# Solenoids.net
KiCad netlist of a schematic drawn in Altium Designer
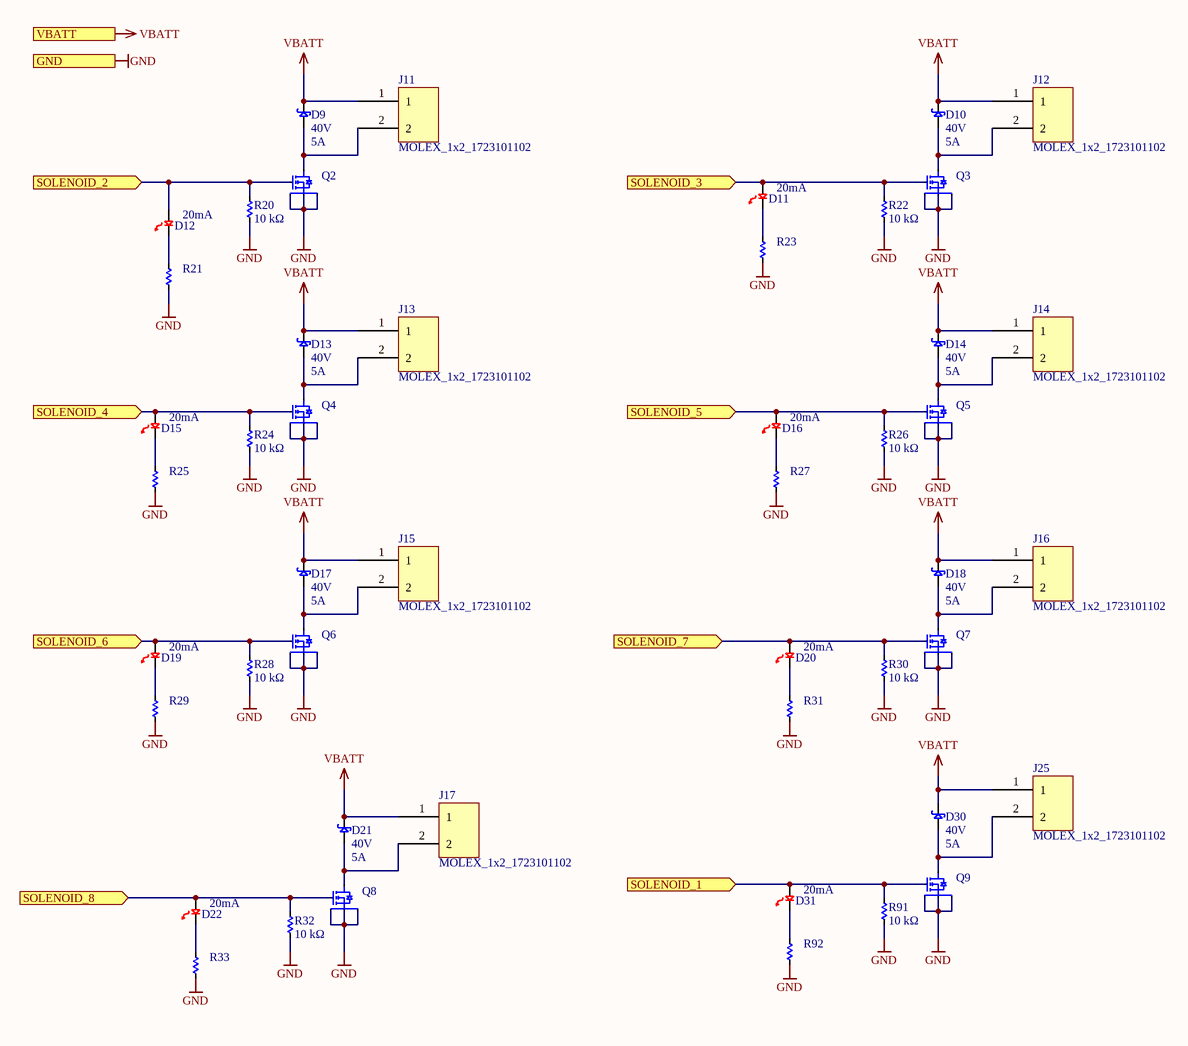
[diagram p0: Solenoids.SchDoc]

(export (version "E")
  (design (tool "Eeschema 10.0.6"))
  (components
    (comp (ref "D9")
      (value "SCHOTTKY_B540C-13-F")
      (footprint "SMC")
      (description "DIODE SCHOTTKY 40V 5A SMC")
      (fields
        (field (name "MANUFACTURER") "Diodes Inc")
        (field (name "MANUFACTURER PART NUMBER") "B540C-13-F")
        (field (name "VOLTAGE - DC REVERSE (VR) (MAX)") "40V")
        (field (name "CURRENT - AVERAGE RECTIFIED (IO)") "5A")
      )
      (libsource (lib "Stanford Student Space Initiative") (part "Symbol"))
    )
    (comp (ref "D10")
      (value "SCHOTTKY_B540C-13-F")
      (footprint "SMC")
      (description "DIODE SCHOTTKY 40V 5A SMC")
      (fields
        (field (name "MANUFACTURER") "Diodes Inc")
        (field (name "MANUFACTURER PART NUMBER") "B540C-13-F")
        (field (name "VOLTAGE - DC REVERSE (VR) (MAX)") "40V")
        (field (name "CURRENT - AVERAGE RECTIFIED (IO)") "5A")
      )
      (libsource (lib "Stanford Student Space Initiative") (part "Symbol"))
    )
    (comp (ref "D11")
      (value "LED_LY974")
      (footprint "0805_Diode")
      (description "LED 0805 RED 20MA")
      (fields
        (field (name "MANUFACTURER") "OSRAM Opto Semiconductors Inc")
        (field (name "MANUFACTURER PART NUMBER") "LH R974-LP-1")
        (field (name "CURRENT - TEST") "20mA")
      )
      (libsource (lib "Stanford Student Space Initiative") (part "LED_LY974"))
    )
    (comp (ref "D12")
      (value "LED_LY974")
      (footprint "0805_Diode")
      (description "LED 0805 RED 20MA")
      (fields
        (field (name "MANUFACTURER") "OSRAM Opto Semiconductors Inc")
        (field (name "MANUFACTURER PART NUMBER") "LH R974-LP-1")
        (field (name "CURRENT - TEST") "20mA")
      )
      (libsource (lib "Stanford Student Space Initiative") (part "LED_LY974"))
    )
    (comp (ref "D13")
      (value "SCHOTTKY_B540C-13-F")
      (footprint "SMC")
      (description "DIODE SCHOTTKY 40V 5A SMC")
      (fields
        (field (name "MANUFACTURER") "Diodes Inc")
        (field (name "MANUFACTURER PART NUMBER") "B540C-13-F")
        (field (name "VOLTAGE - DC REVERSE (VR) (MAX)") "40V")
        (field (name "CURRENT - AVERAGE RECTIFIED (IO)") "5A")
      )
      (libsource (lib "Stanford Student Space Initiative") (part "Symbol"))
    )
    (comp (ref "D14")
      (value "SCHOTTKY_B540C-13-F")
      (footprint "SMC")
      (description "DIODE SCHOTTKY 40V 5A SMC")
      (fields
        (field (name "MANUFACTURER") "Diodes Inc")
        (field (name "MANUFACTURER PART NUMBER") "B540C-13-F")
        (field (name "VOLTAGE - DC REVERSE (VR) (MAX)") "40V")
        (field (name "CURRENT - AVERAGE RECTIFIED (IO)") "5A")
      )
      (libsource (lib "Stanford Student Space Initiative") (part "Symbol"))
    )
    (comp (ref "D15")
      (value "LED_LY974")
      (footprint "0805_Diode")
      (description "LED 0805 RED 20MA")
      (fields
        (field (name "MANUFACTURER") "OSRAM Opto Semiconductors Inc")
        (field (name "MANUFACTURER PART NUMBER") "LH R974-LP-1")
        (field (name "CURRENT - TEST") "20mA")
      )
      (libsource (lib "Stanford Student Space Initiative") (part "LED_LY974"))
    )
    (comp (ref "D16")
      (value "LED_LY974")
      (footprint "0805_Diode")
      (description "LED 0805 RED 20MA")
      (fields
        (field (name "MANUFACTURER") "OSRAM Opto Semiconductors Inc")
        (field (name "MANUFACTURER PART NUMBER") "LH R974-LP-1")
        (field (name "CURRENT - TEST") "20mA")
      )
      (libsource (lib "Stanford Student Space Initiative") (part "LED_LY974"))
    )
    (comp (ref "D17")
      (value "SCHOTTKY_B540C-13-F")
      (footprint "SMC")
      (description "DIODE SCHOTTKY 40V 5A SMC")
      (fields
        (field (name "MANUFACTURER") "Diodes Inc")
        (field (name "MANUFACTURER PART NUMBER") "B540C-13-F")
        (field (name "VOLTAGE - DC REVERSE (VR) (MAX)") "40V")
        (field (name "CURRENT - AVERAGE RECTIFIED (IO)") "5A")
      )
      (libsource (lib "Stanford Student Space Initiative") (part "Symbol"))
    )
    (comp (ref "D18")
      (value "SCHOTTKY_B540C-13-F")
      (footprint "SMC")
      (description "DIODE SCHOTTKY 40V 5A SMC")
      (fields
        (field (name "MANUFACTURER") "Diodes Inc")
        (field (name "MANUFACTURER PART NUMBER") "B540C-13-F")
        (field (name "VOLTAGE - DC REVERSE (VR) (MAX)") "40V")
        (field (name "CURRENT - AVERAGE RECTIFIED (IO)") "5A")
      )
      (libsource (lib "Stanford Student Space Initiative") (part "Symbol"))
    )
    (comp (ref "D19")
      (value "LED_LY974")
      (footprint "0805_Diode")
      (description "LED 0805 RED 20MA")
      (fields
        (field (name "MANUFACTURER") "OSRAM Opto Semiconductors Inc")
        (field (name "MANUFACTURER PART NUMBER") "LH R974-LP-1")
        (field (name "CURRENT - TEST") "20mA")
      )
      (libsource (lib "Stanford Student Space Initiative") (part "LED_LY974"))
    )
    (comp (ref "D20")
      (value "LED_LY974")
      (footprint "0805_Diode")
      (description "LED 0805 RED 20MA")
      (fields
        (field (name "MANUFACTURER") "OSRAM Opto Semiconductors Inc")
        (field (name "MANUFACTURER PART NUMBER") "LH R974-LP-1")
        (field (name "CURRENT - TEST") "20mA")
      )
      (libsource (lib "Stanford Student Space Initiative") (part "LED_LY974"))
    )
    (comp (ref "D21")
      (value "SCHOTTKY_B540C-13-F")
      (footprint "SMC")
      (description "DIODE SCHOTTKY 40V 5A SMC")
      (fields
        (field (name "MANUFACTURER") "Diodes Inc")
        (field (name "MANUFACTURER PART NUMBER") "B540C-13-F")
        (field (name "VOLTAGE - DC REVERSE (VR) (MAX)") "40V")
        (field (name "CURRENT - AVERAGE RECTIFIED (IO)") "5A")
      )
      (libsource (lib "Stanford Student Space Initiative") (part "Symbol"))
    )
    (comp (ref "D22")
      (value "LED_LY974")
      (footprint "0805_Diode")
      (description "LED 0805 RED 20MA")
      (fields
        (field (name "MANUFACTURER") "OSRAM Opto Semiconductors Inc")
        (field (name "MANUFACTURER PART NUMBER") "LH R974-LP-1")
        (field (name "CURRENT - TEST") "20mA")
      )
      (libsource (lib "Stanford Student Space Initiative") (part "LED_LY974"))
    )
    (comp (ref "D30")
      (value "SCHOTTKY_B540C-13-F")
      (footprint "SMC")
      (description "DIODE SCHOTTKY 40V 5A SMC")
      (fields
        (field (name "MANUFACTURER") "Diodes Inc")
        (field (name "MANUFACTURER PART NUMBER") "B540C-13-F")
        (field (name "VOLTAGE - DC REVERSE (VR) (MAX)") "40V")
        (field (name "CURRENT - AVERAGE RECTIFIED (IO)") "5A")
      )
      (libsource (lib "Stanford Student Space Initiative") (part "Symbol"))
    )
    (comp (ref "D31")
      (value "LED_LY974")
      (footprint "0805_Diode")
      (description "LED 0805 RED 20MA")
      (fields
        (field (name "MANUFACTURER") "OSRAM Opto Semiconductors Inc")
        (field (name "MANUFACTURER PART NUMBER") "LH R974-LP-1")
        (field (name "CURRENT - TEST") "20mA")
      )
      (libsource (lib "Stanford Student Space Initiative") (part "LED_LY974"))
    )
    (comp (ref "J11")
      (value "MOLEX_1x2_1723101102")
      (footprint "MOLEX_1x2_1723101102")
      (description "ULTRAFIT CONN HEADER R/A 2POS 3.5MM")
      (libsource (lib "Stanford Student Space Initiative") (part "MOLEX_1x2_1723101102"))
    )
    (comp (ref "J12")
      (value "MOLEX_1x2_1723101102")
      (footprint "MOLEX_1x2_1723101102")
      (description "ULTRAFIT CONN HEADER R/A 2POS 3.5MM")
      (libsource (lib "Stanford Student Space Initiative") (part "MOLEX_1x2_1723101102"))
    )
    (comp (ref "J13")
      (value "MOLEX_1x2_1723101102")
      (footprint "MOLEX_1x2_1723101102")
      (description "ULTRAFIT CONN HEADER R/A 2POS 3.5MM")
      (libsource (lib "Stanford Student Space Initiative") (part "MOLEX_1x2_1723101102"))
    )
    (comp (ref "J14")
      (value "MOLEX_1x2_1723101102")
      (footprint "MOLEX_1x2_1723101102")
      (description "ULTRAFIT CONN HEADER R/A 2POS 3.5MM")
      (libsource (lib "Stanford Student Space Initiative") (part "MOLEX_1x2_1723101102"))
    )
    (comp (ref "J15")
      (value "MOLEX_1x2_1723101102")
      (footprint "MOLEX_1x2_1723101102")
      (description "ULTRAFIT CONN HEADER R/A 2POS 3.5MM")
      (libsource (lib "Stanford Student Space Initiative") (part "MOLEX_1x2_1723101102"))
    )
    (comp (ref "J16")
      (value "MOLEX_1x2_1723101102")
      (footprint "MOLEX_1x2_1723101102")
      (description "ULTRAFIT CONN HEADER R/A 2POS 3.5MM")
      (libsource (lib "Stanford Student Space Initiative") (part "MOLEX_1x2_1723101102"))
    )
    (comp (ref "J17")
      (value "MOLEX_1x2_1723101102")
      (footprint "MOLEX_1x2_1723101102")
      (description "ULTRAFIT CONN HEADER R/A 2POS 3.5MM")
      (libsource (lib "Stanford Student Space Initiative") (part "MOLEX_1x2_1723101102"))
    )
    (comp (ref "J25")
      (value "MOLEX_1x2_1723101102")
      (footprint "MOLEX_1x2_1723101102")
      (description "ULTRAFIT CONN HEADER R/A 2POS 3.5MM")
      (libsource (lib "Stanford Student Space Initiative") (part "MOLEX_1x2_1723101102"))
    )
    (comp (ref "Q2")
      (value "NFET_CSD16323Q3")
      (footprint "8-VSON")
      (description "MOSFET N-CH 25V 3.3X3.3 8-SON")
      (fields
        (field (name "MANUFACTURER") "Texas Instruments")
        (field (name "MANUFACTURER PART NUMBER") "CSD16323Q3")
      )
      (libsource (lib "Stanford Student Space Initiative") (part "NFET_CSD16323Q3"))
    )
    (comp (ref "Q3")
      (value "NFET_CSD16323Q3")
      (footprint "8-VSON")
      (description "MOSFET N-CH 25V 3.3X3.3 8-SON")
      (fields
        (field (name "MANUFACTURER") "Texas Instruments")
        (field (name "MANUFACTURER PART NUMBER") "CSD16323Q3")
      )
      (libsource (lib "Stanford Student Space Initiative") (part "NFET_CSD16323Q3"))
    )
    (comp (ref "Q4")
      (value "NFET_CSD16323Q3")
      (footprint "8-VSON")
      (description "MOSFET N-CH 25V 3.3X3.3 8-SON")
      (fields
        (field (name "MANUFACTURER") "Texas Instruments")
        (field (name "MANUFACTURER PART NUMBER") "CSD16323Q3")
      )
      (libsource (lib "Stanford Student Space Initiative") (part "NFET_CSD16323Q3"))
    )
    (comp (ref "Q5")
      (value "NFET_CSD16323Q3")
      (footprint "8-VSON")
      (description "MOSFET N-CH 25V 3.3X3.3 8-SON")
      (fields
        (field (name "MANUFACTURER") "Texas Instruments")
        (field (name "MANUFACTURER PART NUMBER") "CSD16323Q3")
      )
      (libsource (lib "Stanford Student Space Initiative") (part "NFET_CSD16323Q3"))
    )
    (comp (ref "Q6")
      (value "NFET_CSD16323Q3")
      (footprint "8-VSON")
      (description "MOSFET N-CH 25V 3.3X3.3 8-SON")
      (fields
        (field (name "MANUFACTURER") "Texas Instruments")
        (field (name "MANUFACTURER PART NUMBER") "CSD16323Q3")
      )
      (libsource (lib "Stanford Student Space Initiative") (part "NFET_CSD16323Q3"))
    )
    (comp (ref "Q7")
      (value "NFET_CSD16323Q3")
      (footprint "8-VSON")
      (description "MOSFET N-CH 25V 3.3X3.3 8-SON")
      (fields
        (field (name "MANUFACTURER") "Texas Instruments")
        (field (name "MANUFACTURER PART NUMBER") "CSD16323Q3")
      )
      (libsource (lib "Stanford Student Space Initiative") (part "NFET_CSD16323Q3"))
    )
    (comp (ref "Q8")
      (value "NFET_CSD16323Q3")
      (footprint "8-VSON")
      (description "MOSFET N-CH 25V 3.3X3.3 8-SON")
      (fields
        (field (name "MANUFACTURER") "Texas Instruments")
        (field (name "MANUFACTURER PART NUMBER") "CSD16323Q3")
      )
      (libsource (lib "Stanford Student Space Initiative") (part "NFET_CSD16323Q3"))
    )
    (comp (ref "Q9")
      (value "NFET_CSD16323Q3")
      (footprint "8-VSON")
      (description "MOSFET N-CH 25V 3.3X3.3 8-SON")
      (fields
        (field (name "MANUFACTURER PART NUMBER") "CSD16323Q3")
        (field (name "MANUFACTURER") "Texas Instruments")
      )
      (libsource (lib "Stanford Student Space Initiative") (part "NFET_CSD16323Q3"))
    )
    (comp (ref "R20")
      (value "311-10.0KHRCT-ND")
      (footprint "R0603")
      (description "RES SMD 10K OHM 1% 1/10W 0603")
      (fields
        (field (name "RESISTANCE") "10 kΩ")
        (field (name "MANUFACTURER PART NUMBER") "RC0603FR-0710KL")
        (field (name "MANUFACTURER") "Yageo")
      )
      (libsource (lib "Stanford Student Space Initiative") (part "__template_resistor"))
    )
    (comp (ref "R21")
      (value "311-1.00KHRCT-ND")
      (footprint "R0603")
      (description "RES SMD 1K OHM 1% 1/10W 0603")
      (fields (field (name "MANUFACTURER") "Yageo") (field (name "TOLERANCE") "±1%"))
      (libsource (lib "Stanford Student Space Initiative") (part "__template_resistor"))
    )
    (comp (ref "R22")
      (value "311-10.0KHRCT-ND")
      (footprint "R0603")
      (description "RES SMD 10K OHM 1% 1/10W 0603")
      (fields
        (field (name "RESISTANCE") "10 kΩ")
        (field (name "MANUFACTURER PART NUMBER") "RC0603FR-0710KL")
        (field (name "MANUFACTURER") "Yageo")
      )
      (libsource (lib "Stanford Student Space Initiative") (part "__template_resistor"))
    )
    (comp (ref "R23")
      (value "311-1.00KHRCT-ND")
      (footprint "R0603")
      (description "RES SMD 1K OHM 1% 1/10W 0603")
      (fields (field (name "MANUFACTURER") "Yageo") (field (name "TOLERANCE") "±1%"))
      (libsource (lib "Stanford Student Space Initiative") (part "__template_resistor"))
    )
    (comp (ref "R24")
      (value "311-10.0KHRCT-ND")
      (footprint "R0603")
      (description "RES SMD 10K OHM 1% 1/10W 0603")
      (fields
        (field (name "RESISTANCE") "10 kΩ")
        (field (name "MANUFACTURER PART NUMBER") "RC0603FR-0710KL")
        (field (name "MANUFACTURER") "Yageo")
      )
      (libsource (lib "Stanford Student Space Initiative") (part "__template_resistor"))
    )
    (comp (ref "R25")
      (value "311-1.00KHRCT-ND")
      (footprint "R0603")
      (description "RES SMD 1K OHM 1% 1/10W 0603")
      (fields (field (name "MANUFACTURER") "Yageo") (field (name "TOLERANCE") "±1%"))
      (libsource (lib "Stanford Student Space Initiative") (part "__template_resistor"))
    )
    (comp (ref "R26")
      (value "311-10.0KHRCT-ND")
      (footprint "R0603")
      (description "RES SMD 10K OHM 1% 1/10W 0603")
      (fields
        (field (name "RESISTANCE") "10 kΩ")
        (field (name "MANUFACTURER PART NUMBER") "RC0603FR-0710KL")
        (field (name "MANUFACTURER") "Yageo")
      )
      (libsource (lib "Stanford Student Space Initiative") (part "__template_resistor"))
    )
    (comp (ref "R27")
      (value "311-1.00KHRCT-ND")
      (footprint "R0603")
      (description "RES SMD 1K OHM 1% 1/10W 0603")
      (fields (field (name "MANUFACTURER") "Yageo") (field (name "TOLERANCE") "±1%"))
      (libsource (lib "Stanford Student Space Initiative") (part "__template_resistor"))
    )
    (comp (ref "R28")
      (value "311-10.0KHRCT-ND")
      (footprint "R0603")
      (description "RES SMD 10K OHM 1% 1/10W 0603")
      (fields
        (field (name "RESISTANCE") "10 kΩ")
        (field (name "MANUFACTURER PART NUMBER") "RC0603FR-0710KL")
        (field (name "MANUFACTURER") "Yageo")
      )
      (libsource (lib "Stanford Student Space Initiative") (part "__template_resistor"))
    )
    (comp (ref "R29")
      (value "311-1.00KHRCT-ND")
      (footprint "R0603")
      (description "RES SMD 1K OHM 1% 1/10W 0603")
      (fields (field (name "MANUFACTURER") "Yageo") (field (name "TOLERANCE") "±1%"))
      (libsource (lib "Stanford Student Space Initiative") (part "__template_resistor"))
    )
    (comp (ref "R30")
      (value "311-10.0KHRCT-ND")
      (footprint "R0603")
      (description "RES SMD 10K OHM 1% 1/10W 0603")
      (fields
        (field (name "RESISTANCE") "10 kΩ")
        (field (name "MANUFACTURER PART NUMBER") "RC0603FR-0710KL")
        (field (name "MANUFACTURER") "Yageo")
      )
      (libsource (lib "Stanford Student Space Initiative") (part "__template_resistor"))
    )
    (comp (ref "R31")
      (value "311-1.00KHRCT-ND")
      (footprint "R0603")
      (description "RES SMD 1K OHM 1% 1/10W 0603")
      (fields (field (name "MANUFACTURER") "Yageo") (field (name "TOLERANCE") "±1%"))
      (libsource (lib "Stanford Student Space Initiative") (part "__template_resistor"))
    )
    (comp (ref "R32")
      (value "311-10.0KHRCT-ND")
      (footprint "R0603")
      (description "RES SMD 10K OHM 1% 1/10W 0603")
      (fields
        (field (name "RESISTANCE") "10 kΩ")
        (field (name "MANUFACTURER PART NUMBER") "RC0603FR-0710KL")
        (field (name "MANUFACTURER") "Yageo")
      )
      (libsource (lib "Stanford Student Space Initiative") (part "__template_resistor"))
    )
    (comp (ref "R33")
      (value "311-1.00KHRCT-ND")
      (footprint "R0603")
      (description "RES SMD 1K OHM 1% 1/10W 0603")
      (fields (field (name "MANUFACTURER") "Yageo") (field (name "TOLERANCE") "±1%"))
      (libsource (lib "Stanford Student Space Initiative") (part "__template_resistor"))
    )
    (comp (ref "R91")
      (value "311-10.0KHRCT-ND")
      (footprint "R0603")
      (description "RES SMD 10K OHM 1% 1/10W 0603")
      (fields
        (field (name "RESISTANCE") "10 kΩ")
        (field (name "MANUFACTURER PART NUMBER") "RC0603FR-0710KL")
        (field (name "MANUFACTURER") "Yageo")
      )
      (libsource (lib "Stanford Student Space Initiative") (part "__template_resistor"))
    )
    (comp (ref "R92")
      (value "311-1.00KHRCT-ND")
      (footprint "R0603")
      (description "RES SMD 1K OHM 1% 1/10W 0603")
      (fields (field (name "MANUFACTURER") "Yageo") (field (name "TOLERANCE") "±1%"))
      (libsource (lib "Stanford Student Space Initiative") (part "__template_resistor"))
    )
  )
  (nets
    (net (code "1") (name "/SOLENOID_1") (class "Default")
      (node (ref "D31") (pin "2") (pintype "passive"))
      (node (ref "Q9") (pin "4") (pinfunction "G_4") (pintype "passive"))
      (node (ref "R91") (pin "2") (pintype "passive"))
    )
    (net (code "2") (name "/SOLENOID_2") (class "Default")
      (node (ref "D12") (pin "2") (pintype "passive"))
      (node (ref "Q2") (pin "4") (pinfunction "G_4") (pintype "passive"))
      (node (ref "R20") (pin "2") (pintype "passive"))
    )
    (net (code "3") (name "/SOLENOID_3") (class "Default")
      (node (ref "D11") (pin "2") (pintype "passive"))
      (node (ref "Q3") (pin "4") (pinfunction "G_4") (pintype "passive"))
      (node (ref "R22") (pin "2") (pintype "passive"))
    )
    (net (code "4") (name "/SOLENOID_4") (class "Default")
      (node (ref "D15") (pin "2") (pintype "passive"))
      (node (ref "Q4") (pin "4") (pinfunction "G_4") (pintype "passive"))
      (node (ref "R24") (pin "2") (pintype "passive"))
    )
    (net (code "5") (name "/SOLENOID_5") (class "Default")
      (node (ref "D16") (pin "2") (pintype "passive"))
      (node (ref "Q5") (pin "4") (pinfunction "G_4") (pintype "passive"))
      (node (ref "R26") (pin "2") (pintype "passive"))
    )
    (net (code "6") (name "/SOLENOID_6") (class "Default")
      (node (ref "D19") (pin "2") (pintype "passive"))
      (node (ref "Q6") (pin "4") (pinfunction "G_4") (pintype "passive"))
      (node (ref "R28") (pin "2") (pintype "passive"))
    )
    (net (code "7") (name "/SOLENOID_7") (class "Default")
      (node (ref "D20") (pin "2") (pintype "passive"))
      (node (ref "Q7") (pin "4") (pinfunction "G_4") (pintype "passive"))
      (node (ref "R30") (pin "2") (pintype "passive"))
    )
    (net (code "8") (name "/SOLENOID_8") (class "Default")
      (node (ref "D22") (pin "2") (pintype "passive"))
      (node (ref "Q8") (pin "4") (pinfunction "G_4") (pintype "passive"))
      (node (ref "R32") (pin "2") (pintype "passive"))
    )
    (net (code "9") (name "GND") (class "Default")
      (node (ref "Q2") (pin "1") (pinfunction "S_1") (pintype "passive"))
      (node (ref "Q2") (pin "2") (pinfunction "S_2") (pintype "passive"))
      (node (ref "Q2") (pin "3") (pinfunction "S_3") (pintype "passive"))
      (node (ref "Q3") (pin "1") (pinfunction "S_1") (pintype "passive"))
      (node (ref "Q3") (pin "2") (pinfunction "S_2") (pintype "passive"))
      (node (ref "Q3") (pin "3") (pinfunction "S_3") (pintype "passive"))
      (node (ref "Q4") (pin "1") (pinfunction "S_1") (pintype "passive"))
      (node (ref "Q4") (pin "2") (pinfunction "S_2") (pintype "passive"))
      (node (ref "Q4") (pin "3") (pinfunction "S_3") (pintype "passive"))
      (node (ref "Q5") (pin "1") (pinfunction "S_1") (pintype "passive"))
      (node (ref "Q5") (pin "2") (pinfunction "S_2") (pintype "passive"))
      (node (ref "Q5") (pin "3") (pinfunction "S_3") (pintype "passive"))
      (node (ref "Q6") (pin "1") (pinfunction "S_1") (pintype "passive"))
      (node (ref "Q6") (pin "2") (pinfunction "S_2") (pintype "passive"))
      (node (ref "Q6") (pin "3") (pinfunction "S_3") (pintype "passive"))
      (node (ref "Q7") (pin "1") (pinfunction "S_1") (pintype "passive"))
      (node (ref "Q7") (pin "2") (pinfunction "S_2") (pintype "passive"))
      (node (ref "Q7") (pin "3") (pinfunction "S_3") (pintype "passive"))
      (node (ref "Q8") (pin "1") (pinfunction "S_1") (pintype "passive"))
      (node (ref "Q8") (pin "2") (pinfunction "S_2") (pintype "passive"))
      (node (ref "Q8") (pin "3") (pinfunction "S_3") (pintype "passive"))
      (node (ref "Q9") (pin "1") (pinfunction "S_1") (pintype "passive"))
      (node (ref "Q9") (pin "2") (pinfunction "S_2") (pintype "passive"))
      (node (ref "Q9") (pin "3") (pinfunction "S_3") (pintype "passive"))
      (node (ref "R20") (pin "1") (pintype "passive"))
      (node (ref "R21") (pin "1") (pintype "passive"))
      (node (ref "R22") (pin "1") (pintype "passive"))
      (node (ref "R23") (pin "1") (pintype "passive"))
      (node (ref "R24") (pin "1") (pintype "passive"))
      (node (ref "R25") (pin "1") (pintype "passive"))
      (node (ref "R26") (pin "1") (pintype "passive"))
      (node (ref "R27") (pin "1") (pintype "passive"))
      (node (ref "R28") (pin "1") (pintype "passive"))
      (node (ref "R29") (pin "1") (pintype "passive"))
      (node (ref "R30") (pin "1") (pintype "passive"))
      (node (ref "R31") (pin "1") (pintype "passive"))
      (node (ref "R32") (pin "1") (pintype "passive"))
      (node (ref "R33") (pin "1") (pintype "passive"))
      (node (ref "R91") (pin "1") (pintype "passive"))
      (node (ref "R92") (pin "1") (pintype "passive"))
    )
    (net (code "10") (name "Net-(D11-Pad1)") (class "Default")
      (node (ref "D11") (pin "1") (pintype "passive"))
      (node (ref "R23") (pin "2") (pintype "passive"))
    )
    (net (code "11") (name "Net-(D12-Pad1)") (class "Default")
      (node (ref "D12") (pin "1") (pintype "passive"))
      (node (ref "R21") (pin "2") (pintype "passive"))
    )
    (net (code "12") (name "Net-(D15-Pad1)") (class "Default")
      (node (ref "D15") (pin "1") (pintype "passive"))
      (node (ref "R25") (pin "2") (pintype "passive"))
    )
    (net (code "13") (name "Net-(D16-Pad1)") (class "Default")
      (node (ref "D16") (pin "1") (pintype "passive"))
      (node (ref "R27") (pin "2") (pintype "passive"))
    )
    (net (code "14") (name "Net-(D19-Pad1)") (class "Default")
      (node (ref "D19") (pin "1") (pintype "passive"))
      (node (ref "R29") (pin "2") (pintype "passive"))
    )
    (net (code "15") (name "Net-(D20-Pad1)") (class "Default")
      (node (ref "D20") (pin "1") (pintype "passive"))
      (node (ref "R31") (pin "2") (pintype "passive"))
    )
    (net (code "16") (name "Net-(D22-Pad1)") (class "Default")
      (node (ref "D22") (pin "1") (pintype "passive"))
      (node (ref "R33") (pin "2") (pintype "passive"))
    )
    (net (code "17") (name "Net-(D31-Pad1)") (class "Default")
      (node (ref "D31") (pin "1") (pintype "passive"))
      (node (ref "R92") (pin "2") (pintype "passive"))
    )
    (net (code "18") (name "Net-(Q2-D)") (class "Default")
      (node (ref "D9") (pin "1") (pintype "passive"))
      (node (ref "J11") (pin "2") (pinfunction "2_2") (pintype "passive"))
      (node (ref "Q2") (pin "5") (pinfunction "D_5") (pintype "passive"))
    )
    (net (code "19") (name "Net-(Q3-D)") (class "Default")
      (node (ref "D10") (pin "1") (pintype "passive"))
      (node (ref "J12") (pin "2") (pinfunction "2_2") (pintype "passive"))
      (node (ref "Q3") (pin "5") (pinfunction "D_5") (pintype "passive"))
    )
    (net (code "20") (name "Net-(Q4-D)") (class "Default")
      (node (ref "D13") (pin "1") (pintype "passive"))
      (node (ref "J13") (pin "2") (pinfunction "2_2") (pintype "passive"))
      (node (ref "Q4") (pin "5") (pinfunction "D_5") (pintype "passive"))
    )
    (net (code "21") (name "Net-(Q5-D)") (class "Default")
      (node (ref "D14") (pin "1") (pintype "passive"))
      (node (ref "J14") (pin "2") (pinfunction "2_2") (pintype "passive"))
      (node (ref "Q5") (pin "5") (pinfunction "D_5") (pintype "passive"))
    )
    (net (code "22") (name "Net-(Q6-D)") (class "Default")
      (node (ref "D17") (pin "1") (pintype "passive"))
      (node (ref "J15") (pin "2") (pinfunction "2_2") (pintype "passive"))
      (node (ref "Q6") (pin "5") (pinfunction "D_5") (pintype "passive"))
    )
    (net (code "23") (name "Net-(Q7-D)") (class "Default")
      (node (ref "D18") (pin "1") (pintype "passive"))
      (node (ref "J16") (pin "2") (pinfunction "2_2") (pintype "passive"))
      (node (ref "Q7") (pin "5") (pinfunction "D_5") (pintype "passive"))
    )
    (net (code "24") (name "Net-(Q8-D)") (class "Default")
      (node (ref "D21") (pin "1") (pintype "passive"))
      (node (ref "J17") (pin "2") (pinfunction "2_2") (pintype "passive"))
      (node (ref "Q8") (pin "5") (pinfunction "D_5") (pintype "passive"))
    )
    (net (code "25") (name "Net-(Q9-D)") (class "Default")
      (node (ref "D30") (pin "1") (pintype "passive"))
      (node (ref "J25") (pin "2") (pinfunction "2_2") (pintype "passive"))
      (node (ref "Q9") (pin "5") (pinfunction "D_5") (pintype "passive"))
    )
    (net (code "26") (name "VBATT") (class "Default")
      (node (ref "D10") (pin "2") (pintype "passive"))
      (node (ref "D13") (pin "2") (pintype "passive"))
      (node (ref "D14") (pin "2") (pintype "passive"))
      (node (ref "D17") (pin "2") (pintype "passive"))
      (node (ref "D18") (pin "2") (pintype "passive"))
      (node (ref "D21") (pin "2") (pintype "passive"))
      (node (ref "D30") (pin "2") (pintype "passive"))
      (node (ref "D9") (pin "2") (pintype "passive"))
      (node (ref "J11") (pin "1") (pinfunction "1_1") (pintype "passive"))
      (node (ref "J12") (pin "1") (pinfunction "1_1") (pintype "passive"))
      (node (ref "J13") (pin "1") (pinfunction "1_1") (pintype "passive"))
      (node (ref "J14") (pin "1") (pinfunction "1_1") (pintype "passive"))
      (node (ref "J15") (pin "1") (pinfunction "1_1") (pintype "passive"))
      (node (ref "J16") (pin "1") (pinfunction "1_1") (pintype "passive"))
      (node (ref "J17") (pin "1") (pinfunction "1_1") (pintype "passive"))
      (node (ref "J25") (pin "1") (pinfunction "1_1") (pintype "passive"))
    )
  )
)
